# 01_Power.net
KiCad netlist of a schematic drawn in Altium Designer
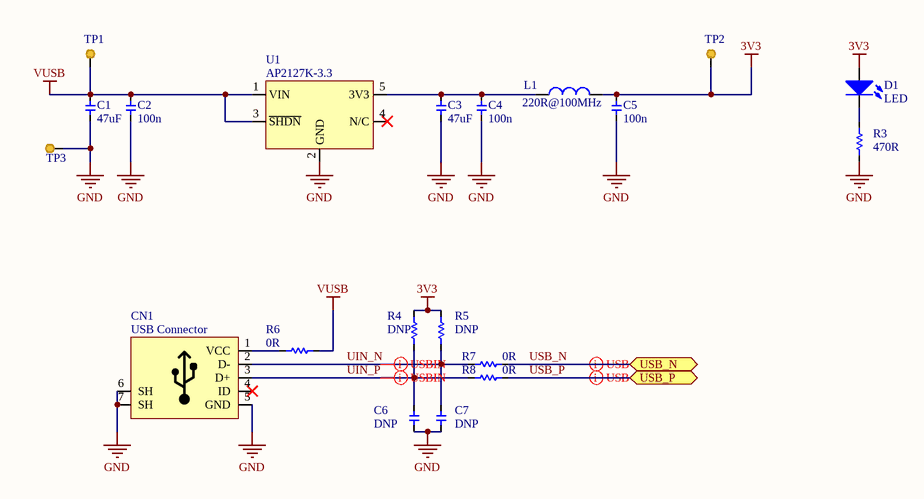
[diagram p0: 01_Power.SchDoc]

(export (version "E")
  (design (tool "Eeschema 10.0.6"))
  (components
    (comp (ref "C1")
      (value "47uF")
      (footprint "Moji Footprintovi:0805")
      (description "CAP TANT POLY47UF 20% 16V 1210")
      (fields
        (field (name "MANUFACTURER") "AVX Corporation")
        (field (name "MANUFACTURER PART NUMBER") "TCNT476M016R0200A")
      )
      (libsource (lib "Moji Schematici") (part "Cap"))
    )
    (comp (ref "C2")
      (value "100n")
      (footprint "Moji Footprintovi:0603 - CAP")
      (description "Capacitor")
      (fields
        (field (name "MANUFACTURER") "AVX Corporation")
        (field (name "MANUFACTURER PART NUMBER") "06035C104KAT2A")
      )
      (libsource (lib "Moji Schematici") (part "Cap"))
    )
    (comp (ref "C3")
      (value "47uF")
      (footprint "Moji Footprintovi:0805")
      (description "CAP TANT POLY47UF 20% 16V 1210")
      (fields
        (field (name "MANUFACTURER") "AVX Corporation")
        (field (name "MANUFACTURER PART NUMBER") "TCNT476M016R0200A")
      )
      (libsource (lib "Moji Schematici") (part "Cap"))
    )
    (comp (ref "C4")
      (value "100n")
      (footprint "Moji Footprintovi:0603 - CAP")
      (description "Capacitor")
      (fields
        (field (name "MANUFACTURER") "AVX Corporation")
        (field (name "MANUFACTURER PART NUMBER") "06035C104KAT2A")
      )
      (libsource (lib "Moji Schematici") (part "Cap"))
    )
    (comp (ref "C5")
      (value "100n")
      (footprint "Moji Footprintovi:0603 - CAP")
      (description "Capacitor")
      (fields
        (field (name "MANUFACTURER") "AVX Corporation")
        (field (name "MANUFACTURER PART NUMBER") "06035C104KAT2A")
      )
      (libsource (lib "Moji Schematici") (part "Cap"))
    )
    (comp (ref "C6")
      (value "DNP")
      (footprint "Moji Footprintovi:0603 - CAP")
      (description "Capacitor")
      (fields
        (field (name "MANUFACTURER") "AVX Corporation")
        (field (name "MANUFACTURER PART NUMBER") "06035C104KAT2A")
      )
      (libsource (lib "Moji Schematici") (part "Cap"))
    )
    (comp (ref "C7")
      (value "DNP")
      (footprint "Moji Footprintovi:0603 - CAP")
      (description "Capacitor")
      (fields
        (field (name "MANUFACTURER") "AVX Corporation")
        (field (name "MANUFACTURER PART NUMBER") "06035C104KAT2A")
      )
      (libsource (lib "Moji Schematici") (part "Cap"))
    )
    (comp (ref "CN1")
      (value "USB Connector")
      (footprint "Moji Footprintovi:Amphenol FCI 10118192-0001LF")
      (description "CONN USB MICRO B RECPT SMT R/A")
      (fields
        (field (name "MANUFACTURER") "Amphenol FCI")
        (field (name "DISTRIBUTOR PART NUMBER") "609-4613-1-ND")
      )
      (libsource (lib "Moji Schematici") (part "Amphenol FCI 10118192-0001LF"))
    )
    (comp (ref "D1")
      (value "LED")
      (footprint "Moji Footprintovi:0603 Diode")
      (description "Typical RED GaAs LED")
      (libsource (lib "Moji Schematici") (part "LED"))
    )
    (comp (ref "L1")
      (value "220R@100MHz")
      (footprint "Moji Footprintovi:0603")
      (description "FERRITE BEAD 220 OHM 0603 1LN")
      (fields
        (field (name "MANUFACTURER") "Murata Electronics North America")
        (field (name "MANUFACTURER PART NUMBER") "BLM18KG221SN1D")
      )
      (libsource (lib "Moji Schematici") (part "Inductor"))
    )
    (comp (ref "R3")
      (value "470R")
      (footprint "Moji Footprintovi:0603")
      (description "Resistor")
      (fields
        (field (name "MANUFACTURER") "Yageo")
        (field (name "MANUFACTURER PART NUMBER") "RC0603FR-07470RL")
      )
      (libsource (lib "Moji Schematici") (part "Res"))
    )
    (comp (ref "R4")
      (value "DNP")
      (footprint "Moji Footprintovi:0603")
      (description "Resistor")
      (fields
        (field (name "MANUFACTURER") "Yageo")
        (field (name "MANUFACTURER PART NUMBER") "RC0603JR-070RL")
      )
      (libsource (lib "Moji Schematici") (part "Res"))
    )
    (comp (ref "R5")
      (value "DNP")
      (footprint "Moji Footprintovi:0603")
      (description "Resistor")
      (fields
        (field (name "MANUFACTURER") "Yageo")
        (field (name "MANUFACTURER PART NUMBER") "RC0603JR-070RL")
      )
      (libsource (lib "Moji Schematici") (part "Res"))
    )
    (comp (ref "R6")
      (value "0R")
      (footprint "Moji Footprintovi:0603")
      (description "Resistor")
      (fields
        (field (name "MANUFACTURER") "Yageo")
        (field (name "MANUFACTURER PART NUMBER") "RC0603JR-070RL")
      )
      (libsource (lib "Moji Schematici") (part "Res"))
    )
    (comp (ref "R7")
      (value "0R")
      (footprint "Moji Footprintovi:0603")
      (description "Resistor")
      (fields
        (field (name "MANUFACTURER") "Yageo")
        (field (name "MANUFACTURER PART NUMBER") "RC0603JR-070RL")
      )
      (libsource (lib "Moji Schematici") (part "Res"))
    )
    (comp (ref "R8")
      (value "0R")
      (footprint "Moji Footprintovi:0603")
      (description "Resistor")
      (fields
        (field (name "MANUFACTURER") "Yageo")
        (field (name "MANUFACTURER PART NUMBER") "RC0603JR-070RL")
      )
      (libsource (lib "Moji Schematici") (part "Res"))
    )
    (comp (ref "TP1")
      (value "Test Point 0.6mm")
      (footprint "Moji Footprintovi:TP_SMD_1mm")
      (libsource (lib "Moji Schematici") (part "TP"))
    )
    (comp (ref "TP2")
      (value "Test Point 0.6mm")
      (footprint "Moji Footprintovi:TP_SMD_1mm")
      (libsource (lib "Moji Schematici") (part "TP"))
    )
    (comp (ref "TP3")
      (value "Test Point 0.6mm")
      (footprint "Moji Footprintovi:TP_SMD_1mm")
      (libsource (lib "Moji Schematici") (part "TP"))
    )
    (comp (ref "U1")
      (value "AP2127K-3.3")
      (footprint "Moji Footprintovi:SOT-23-5")
      (description "IC REG LINEAR 3.3V 300MA SOT23-5")
      (fields
        (field (name "DISTRIBUTOR PART NUMBER") "AP2127K-3.3TRG1DICT-ND")
        (field (name "MANUFACTURER") "Diodes Incorporated")
      )
      (libsource (lib "Moji Schematici") (part "AP2127K-3.3TRG1"))
    )
  )
  (nets
    (net (code "1") (name "/UIN_N") (class "Default")
      (node (ref "C7") (pin "2") (pinfunction "2_2") (pintype "passive"))
      (node (ref "CN1") (pin "2") (pinfunction "D-_2") (pintype "passive"))
      (node (ref "R5") (pin "2") (pinfunction "2_2") (pintype "passive"))
      (node (ref "R7") (pin "2") (pinfunction "2_2") (pintype "passive"))
    )
    (net (code "2") (name "/UIN_P") (class "Default")
      (node (ref "C6") (pin "2") (pinfunction "2_2") (pintype "passive"))
      (node (ref "CN1") (pin "3") (pinfunction "D+_3") (pintype "passive"))
      (node (ref "R4") (pin "2") (pinfunction "2_2") (pintype "passive"))
      (node (ref "R8") (pin "2") (pinfunction "2_2") (pintype "passive"))
    )
    (net (code "3") (name "/USB_N") (class "Default")
      (node (ref "R7") (pin "1") (pinfunction "1_1") (pintype "passive"))
    )
    (net (code "4") (name "/USB_P") (class "Default")
      (node (ref "R8") (pin "1") (pinfunction "1_1") (pintype "passive"))
    )
    (net (code "5") (name "3V3") (class "Default")
      (node (ref "C5") (pin "2") (pinfunction "2_2") (pintype "passive"))
      (node (ref "D1") (pin "A") (pinfunction "A_A") (pintype "passive"))
      (node (ref "L1") (pin "2") (pinfunction "2_2") (pintype "passive"))
      (node (ref "R4") (pin "1") (pinfunction "1_1") (pintype "passive"))
      (node (ref "R5") (pin "1") (pinfunction "1_1") (pintype "passive"))
      (node (ref "TP2") (pin "1") (pinfunction "1_1") (pintype "passive"))
    )
    (net (code "6") (name "GND") (class "Default")
      (node (ref "C1") (pin "1") (pinfunction "1_1") (pintype "passive"))
      (node (ref "C2") (pin "1") (pinfunction "1_1") (pintype "passive"))
      (node (ref "C3") (pin "1") (pinfunction "1_1") (pintype "passive"))
      (node (ref "C4") (pin "1") (pinfunction "1_1") (pintype "passive"))
      (node (ref "C5") (pin "1") (pinfunction "1_1") (pintype "passive"))
      (node (ref "C6") (pin "1") (pinfunction "1_1") (pintype "passive"))
      (node (ref "C7") (pin "1") (pinfunction "1_1") (pintype "passive"))
      (node (ref "CN1") (pin "5") (pinfunction "GND_5") (pintype "passive"))
      (node (ref "CN1") (pin "6") (pinfunction "SH_6") (pintype "passive"))
      (node (ref "CN1") (pin "7") (pinfunction "SH_7") (pintype "passive"))
      (node (ref "R3") (pin "2") (pinfunction "2_2") (pintype "passive"))
      (node (ref "TP3") (pin "1") (pinfunction "1_1") (pintype "passive"))
      (node (ref "U1") (pin "2") (pinfunction "GND_2") (pintype "passive"))
    )
    (net (code "7") (name "Net-(CN1-VCC)") (class "Default")
      (node (ref "CN1") (pin "1") (pinfunction "VCC_1") (pintype "passive"))
      (node (ref "R6") (pin "2") (pinfunction "2_2") (pintype "passive"))
    )
    (net (code "8") (name "Net-(D1-PadK)") (class "Default")
      (node (ref "D1") (pin "K") (pinfunction "K_K") (pintype "passive"))
      (node (ref "R3") (pin "1") (pinfunction "1_1") (pintype "passive"))
    )
    (net (code "9") (name "Net-(U1-3V3)") (class "Default")
      (node (ref "C3") (pin "2") (pinfunction "2_2") (pintype "passive"))
      (node (ref "C4") (pin "2") (pinfunction "2_2") (pintype "passive"))
      (node (ref "L1") (pin "1") (pinfunction "1_1") (pintype "passive"))
      (node (ref "U1") (pin "5") (pinfunction "3V3_5") (pintype "passive"))
    )
    (net (code "10") (name "VUSB") (class "Default")
      (node (ref "C1") (pin "2") (pinfunction "2_2") (pintype "passive"))
      (node (ref "C2") (pin "2") (pinfunction "2_2") (pintype "passive"))
      (node (ref "R6") (pin "1") (pinfunction "1_1") (pintype "passive"))
      (node (ref "TP1") (pin "1") (pinfunction "1_1") (pintype "passive"))
      (node (ref "U1") (pin "1") (pinfunction "VIN_1") (pintype "passive"))
      (node (ref "U1") (pin "3") (pinfunction "~{SHDN}_3") (pintype "passive"))
    )
    (net (code "11") (name "unconnected-(CN1-ID-Pad4)") (class "Default")
      (node (ref "CN1") (pin "4") (pinfunction "ID_4") (pintype "passive+no_connect"))
    )
    (net (code "12") (name "unconnected-(U1-N{slash}C-Pad4)") (class "Default")
      (node (ref "U1") (pin "4") (pinfunction "N/C_4") (pintype "passive+no_connect"))
    )
  )
)
